# V2.net
KiCad netlist of a schematic drawn in Altium Designer
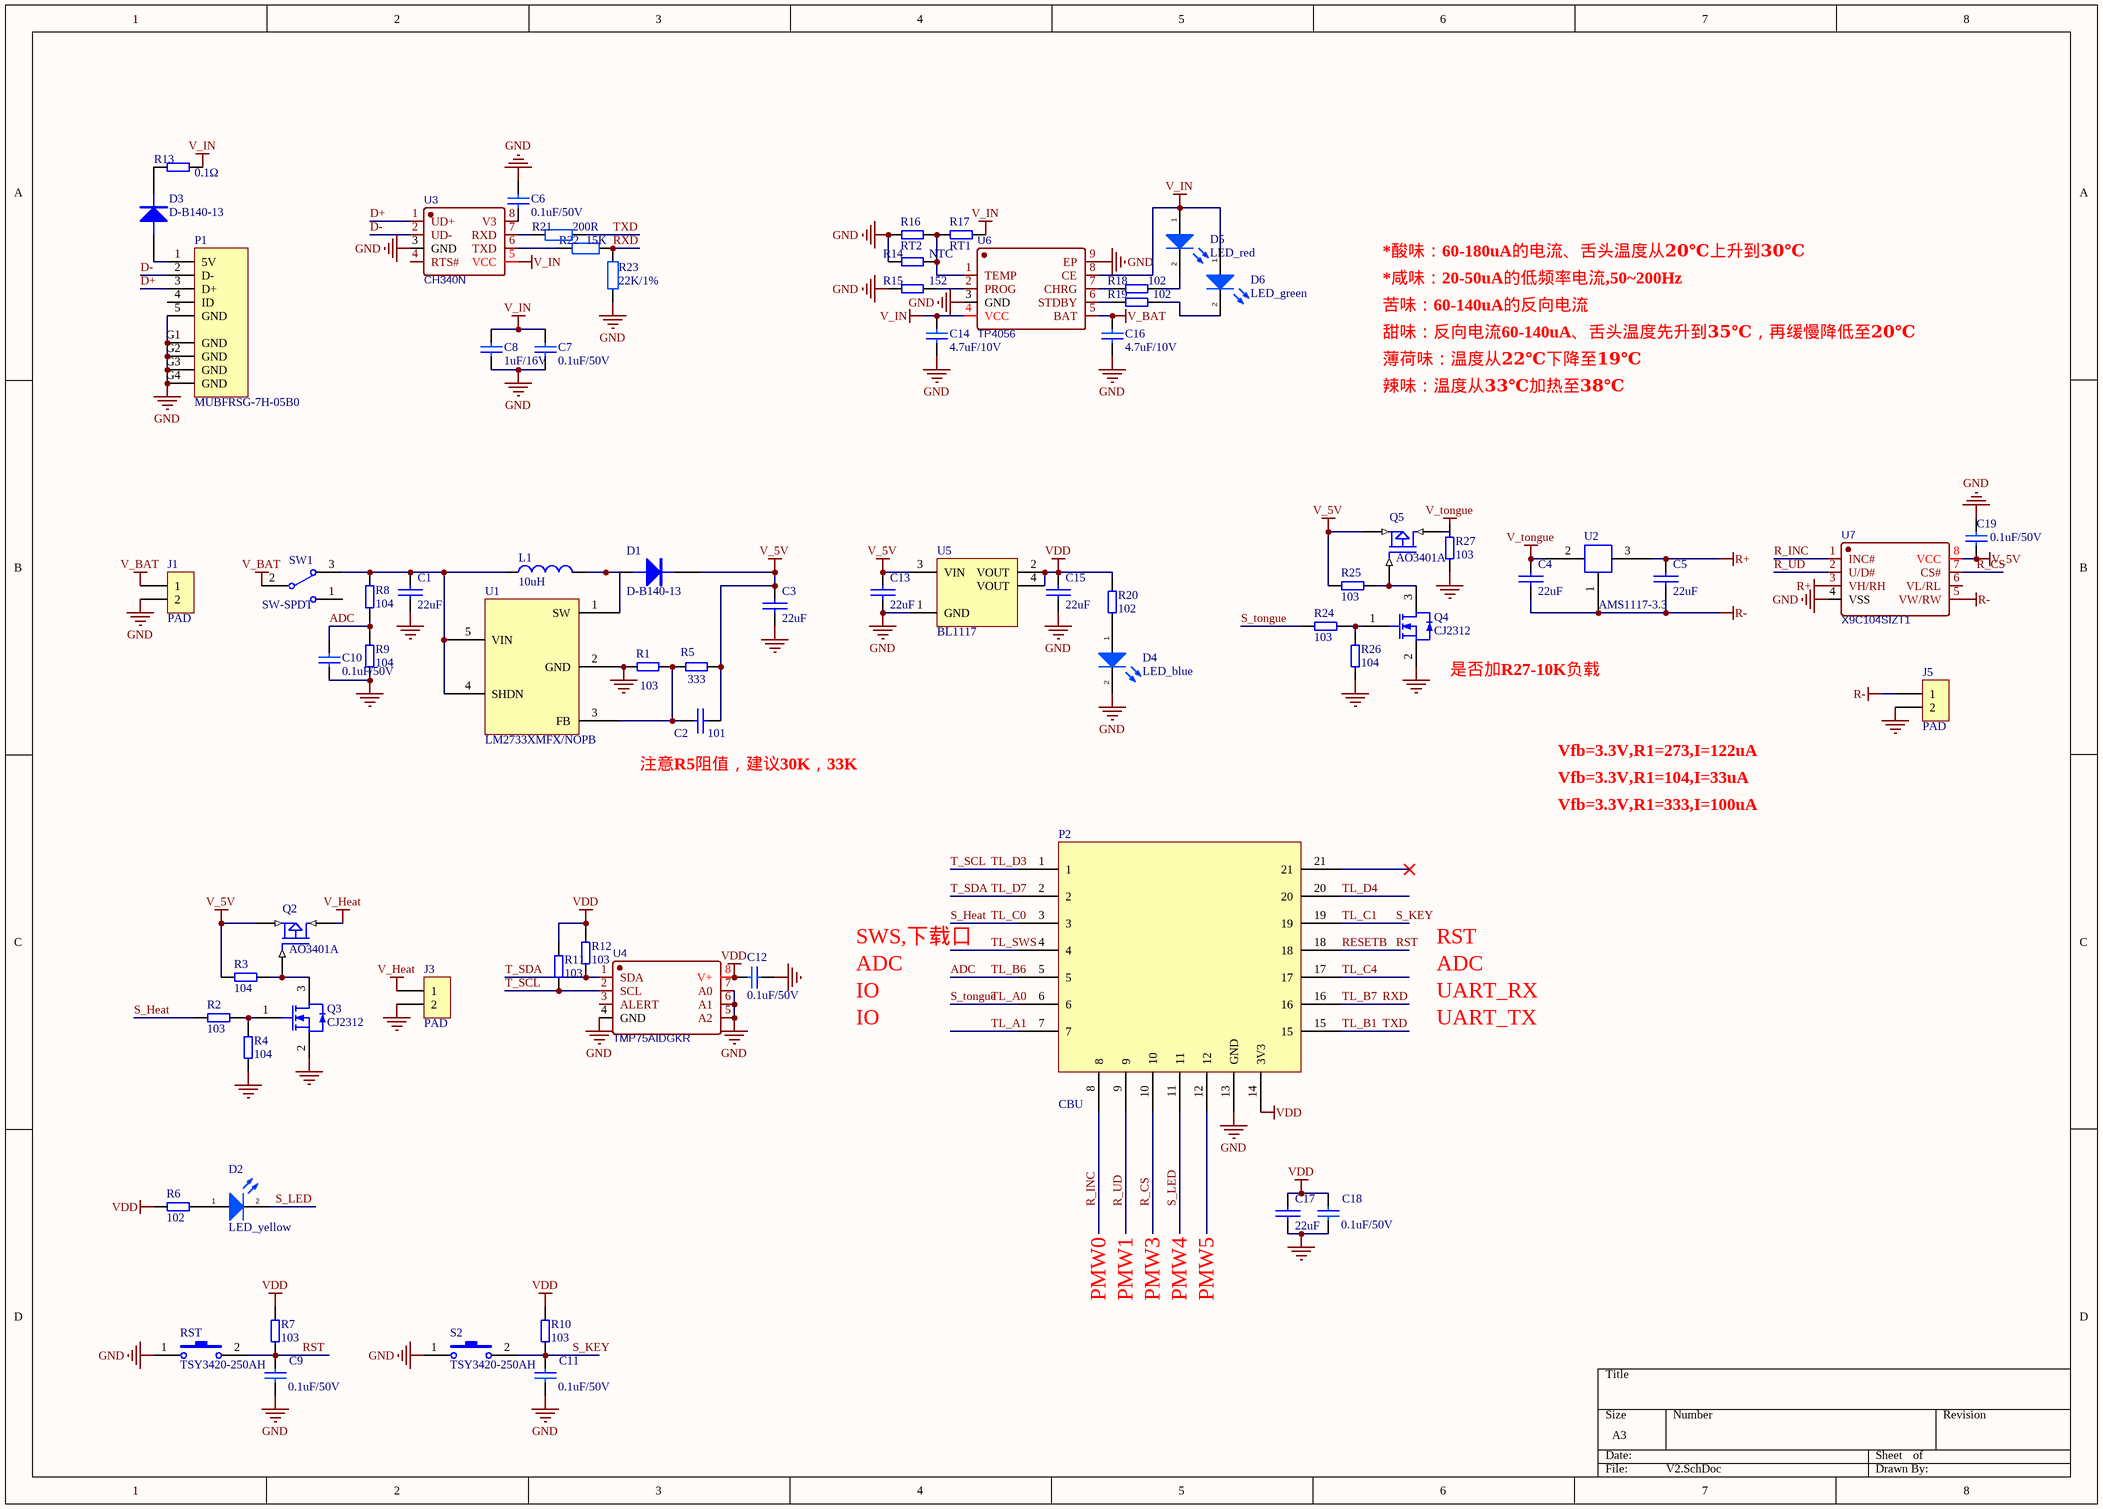
[diagram p0: V2.SchDoc]

(export (version "E")
  (design (tool "Eeschema 10.0.6"))
  (components
    (comp (ref "C1") (value "22uF") (footprint "C1206") (libsource (lib "altium-import") (part "root_0_C1_")))
    (comp (ref "C2")
      (value "101")
      (footprint "C0603")
      (description "Capacitor")
      (libsource (lib "先锋器件封装库") (part "CAP"))
    )
    (comp (ref "C3") (value "22uF") (footprint "C1206") (libsource (lib "altium-import") (part "root_0_C1_")))
    (comp (ref "C4") (value "22uF") (footprint "C1206") (libsource (lib "altium-import") (part "root_0_C1_")))
    (comp (ref "C5") (value "22uF") (footprint "C1206") (libsource (lib "altium-import") (part "root_0_C1_")))
    (comp (ref "C6")
      (value "0.1uF/50V")
      (footprint "C0603_GRM18")
      (description "无极性电容")
      (fields (field (name "PART NUMBER") "1.02.05.00834") (field (name "修改人") "system"))
      (libsource (lib "Database_Libs") (part "Capacitor - non polarized"))
    )
    (comp (ref "C7")
      (value "0.1uF/50V")
      (footprint "C0603_GRM18")
      (description "无极性电容")
      (fields (field (name "PART NUMBER") "1.02.05.00834") (field (name "修改人") "system"))
      (libsource (lib "Database_Libs") (part "Capacitor - non polarized"))
    )
    (comp (ref "C8")
      (value "1uF/16V")
      (footprint "C0603_GRM18")
      (description "无极性电容")
      (fields (field (name "PART NUMBER") "1.02.03.00181") (field (name "修改人") "system"))
      (libsource (lib "Database_Libs") (part "Capacitor - non polarized"))
    )
    (comp (ref "C9")
      (value "0.1uF/50V")
      (footprint "C0603_GRM18")
      (description "无极性电容")
      (fields (field (name "PART NUMBER") "1.02.05.00150") (field (name "修改人") "system"))
      (libsource (lib "Database_Libs") (part "Capacitor - non polarized"))
    )
    (comp (ref "C10")
      (value "0.1uF/50V")
      (footprint "C0603_GRM18")
      (description "无极性电容")
      (fields (field (name "PART NUMBER") "1.02.05.00150") (field (name "修改人") "system"))
      (libsource (lib "Database_Libs") (part "Capacitor - non polarized"))
    )
    (comp (ref "C11")
      (value "0.1uF/50V")
      (footprint "C0603_GRM18")
      (description "无极性电容")
      (fields (field (name "PART NUMBER") "1.02.05.00150") (field (name "修改人") "system"))
      (libsource (lib "Database_Libs") (part "Capacitor - non polarized"))
    )
    (comp (ref "C12")
      (value "0.1uF/50V")
      (footprint "C0603_GRM18")
      (description "无极性电容")
      (fields (field (name "PART NUMBER") "1.02.05.00150") (field (name "修改人") "system"))
      (libsource (lib "Database_Libs") (part "Capacitor - non polarized"))
    )
    (comp (ref "C13")
      (value "22uF")
      (footprint "C1206")
      (libsource (lib "altium-import") (part "root_0_C1_"))
    )
    (comp (ref "C14")
      (value "4.7uF/10V")
      (footprint "C0603_GRM18")
      (description "无极性电容")
      (fields (field (name "PART NUMBER") "1.02.05.00710") (field (name "修改人") "system"))
      (libsource (lib "Database_Libs") (part "Capacitor - non polarized"))
    )
    (comp (ref "C15")
      (value "22uF")
      (footprint "C1206")
      (libsource (lib "altium-import") (part "root_0_C1_"))
    )
    (comp (ref "C16")
      (value "4.7uF/10V")
      (footprint "C0603_GRM18")
      (description "无极性电容")
      (fields (field (name "PART NUMBER") "1.02.05.00710") (field (name "修改人") "system"))
      (libsource (lib "Database_Libs") (part "Capacitor - non polarized"))
    )
    (comp (ref "C17")
      (value "22uF")
      (footprint "C1206")
      (libsource (lib "altium-import") (part "root_0_C1_"))
    )
    (comp (ref "C18")
      (value "0.1uF/50V")
      (footprint "C0603_GRM18")
      (description "无极性电容")
      (fields (field (name "PART NUMBER") "1.02.05.00150") (field (name "修改人") "system"))
      (libsource (lib "Database_Libs") (part "Capacitor - non polarized"))
    )
    (comp (ref "C19")
      (value "0.1uF/50V")
      (footprint "C0603_GRM18")
      (description "无极性电容")
      (fields (field (name "PART NUMBER") "1.02.05.00150") (field (name "修改人") "system"))
      (libsource (lib "Database_Libs") (part "Capacitor - non polarized"))
    )
    (comp (ref "D1")
      (value "D-B140-13")
      (footprint "XF-SS12C")
      (description "Diode")
      (fields (field (name "SPECIFICATION") "D-B140-13"))
      (libsource (lib "先锋器件封装库") (part "DIODE"))
    )
    (comp (ref "D2")
      (value "LED_yellow")
      (footprint "LED0603")
      (description "LED")
      (fields (field (name "PART NUMBER") "1.06.02.00449") (field (name "修改人") "system"))
      (libsource (lib "Database_Libs") (part "LED"))
    )
    (comp (ref "D3")
      (value "D-B140-13")
      (footprint "XF-SS12C")
      (description "Diode")
      (fields (field (name "SPECIFICATION") "D-B140-13"))
      (libsource (lib "先锋器件封装库") (part "DIODE"))
    )
    (comp (ref "D4")
      (value "LED_blue")
      (footprint "LED0603")
      (description "LED")
      (fields (field (name "PART NUMBER") "1.06.02.00449") (field (name "修改人") "system"))
      (libsource (lib "Database_Libs") (part "LED"))
    )
    (comp (ref "D5")
      (value "LED_red")
      (footprint "LED0603")
      (description "LED")
      (fields (field (name "PART NUMBER") "1.06.02.00449") (field (name "修改人") "system"))
      (libsource (lib "Database_Libs") (part "LED"))
    )
    (comp (ref "D6")
      (value "LED_green")
      (footprint "LED0603")
      (description "LED")
      (fields (field (name "PART NUMBER") "1.06.02.00449") (field (name "修改人") "system"))
      (libsource (lib "Database_Libs") (part "LED"))
    )
    (comp (ref "J1")
      (value "PAD")
      (footprint "POW_5#")
      (description "Connector")
      (libsource (lib "altium-import") (part "root_0_CON2_"))
    )
    (comp (ref "J3")
      (value "PAD")
      (footprint "HDR1X2")
      (description "Connector")
      (libsource (lib "接插件") (part "CON2"))
    )
    (comp (ref "J5")
      (value "PAD")
      (footprint "HDR1X2")
      (description "Connector")
      (libsource (lib "接插件") (part "CON2"))
    )
    (comp (ref "L1")
      (value "10uH")
      (footprint "CD73")
      (description "Inductor")
      (fields (field (name "Comment") "4.7uH") (field (name "PUBLISHER") "Altium Limited"))
      (libsource (lib "altium-import") (part "root_0_Inductor_"))
    )
    (comp (ref "P1")
      (value "MUBFRSG-7H-05B0")
      (footprint "MIRCOUSB_5PIN-A")
      (description "USB")
      (fields (field (name "PART NUMBER") "1.16.99.00399") (field (name "修改人") "system"))
      (libsource (lib "Database_Libs") (part "USB_5p"))
    )
    (comp (ref "P2")
      (value "CBU")
      (footprint "PcbLib_Tuya:CBU-PCBA")
      (fields (field (name "PART NUMBER") "0110"))
      (libsource (lib "Database_Libs1") (part "CBU"))
    )
    (comp (ref "Q2")
      (value "AO3401A")
      (footprint "SOT-23")
      (description "MOSFET-P")
      (fields (field (name "SPECIFICATION") "AO3401A"))
      (libsource (lib "先锋器件封装库") (part "MOSFET-P"))
    )
    (comp (ref "Q3")
      (value "CJ2312")
      (footprint "SOT23-3")
      (description "N-Channel MOSFET")
      (fields
        (field (name "PART NUMBER") "1.06.11.00008")
        (field (name "ORCAD LIBRARY PATH") "‪Z:\\tuya_lib\\sch-lib\\DISCRETE.OLB")
        (field (name "修改人") "system")
      )
      (libsource (lib "Database_Libs") (part "MOSFET-N"))
    )
    (comp (ref "Q4")
      (value "CJ2312")
      (footprint "SOT23-3")
      (description "N-Channel MOSFET")
      (fields
        (field (name "PART NUMBER") "1.06.11.00008")
        (field (name "ORCAD LIBRARY PATH") "‪Z:\\tuya_lib\\sch-lib\\DISCRETE.OLB")
        (field (name "修改人") "system")
      )
      (libsource (lib "Database_Libs") (part "MOSFET-N"))
    )
    (comp (ref "Q5")
      (value "AO3401A")
      (footprint "SOT-23")
      (description "MOSFET-P")
      (fields (field (name "SPECIFICATION") "AO3401A"))
      (libsource (lib "先锋器件封装库") (part "MOSFET-P"))
    )
    (comp (ref "R1")
      (value "103")
      (footprint "R0603")
      (description "RES")
      (libsource (lib "先锋器件封装库") (part "RES-1"))
    )
    (comp (ref "R2")
      (value "103")
      (footprint "R0603")
      (description "RES")
      (libsource (lib "先锋器件封装库") (part "RES-1"))
    )
    (comp (ref "R3")
      (value "104")
      (footprint "R0603")
      (description "RES")
      (libsource (lib "先锋器件封装库") (part "RES-1"))
    )
    (comp (ref "R4")
      (value "104")
      (footprint "R0603")
      (description "RES")
      (libsource (lib "先锋器件封装库") (part "RES-1"))
    )
    (comp (ref "R5")
      (value "333")
      (footprint "R0603")
      (description "RES")
      (libsource (lib "先锋器件封装库") (part "RES-1"))
    )
    (comp (ref "R6")
      (value "102")
      (footprint "R0603")
      (description "RES")
      (libsource (lib "先锋器件封装库") (part "RES-1"))
    )
    (comp (ref "R7")
      (value "103")
      (footprint "R0603")
      (description "RES")
      (libsource (lib "先锋器件封装库") (part "RES-1"))
    )
    (comp (ref "R8")
      (value "104")
      (footprint "R0603")
      (description "RES")
      (libsource (lib "先锋器件封装库") (part "RES-1"))
    )
    (comp (ref "R9")
      (value "104")
      (footprint "R0603")
      (description "RES")
      (libsource (lib "先锋器件封装库") (part "RES-1"))
    )
    (comp (ref "R10")
      (value "103")
      (footprint "R0603")
      (description "RES")
      (libsource (lib "先锋器件封装库") (part "RES-1"))
    )
    (comp (ref "R11")
      (value "103")
      (footprint "R0603")
      (description "RES")
      (libsource (lib "先锋器件封装库") (part "RES-1"))
    )
    (comp (ref "R12")
      (value "103")
      (footprint "R0603")
      (description "RES")
      (libsource (lib "先锋器件封装库") (part "RES-1"))
    )
    (comp (ref "R13")
      (value "0.1Ω")
      (footprint "R0603")
      (description "RES")
      (libsource (lib "先锋器件封装库") (part "RES-1"))
    )
    (comp (ref "R14")
      (value "NTC")
      (footprint "R0603")
      (description "RES")
      (libsource (lib "先锋器件封装库") (part "RES-1"))
    )
    (comp (ref "R15")
      (value "152")
      (footprint "R0603")
      (description "RES")
      (libsource (lib "先锋器件封装库") (part "RES-1"))
    )
    (comp (ref "R16")
      (value "RT2")
      (footprint "R0603")
      (description "RES")
      (libsource (lib "先锋器件封装库") (part "RES-1"))
    )
    (comp (ref "R17")
      (value "RT1")
      (footprint "R0603")
      (description "RES")
      (libsource (lib "先锋器件封装库") (part "RES-1"))
    )
    (comp (ref "R18")
      (value "102")
      (footprint "R0603")
      (description "RES")
      (libsource (lib "先锋器件封装库") (part "RES-1"))
    )
    (comp (ref "R19")
      (value "102")
      (footprint "R0603")
      (description "RES")
      (libsource (lib "先锋器件封装库") (part "RES-1"))
    )
    (comp (ref "R20")
      (value "102")
      (footprint "R0603")
      (description "RES")
      (libsource (lib "先锋器件封装库") (part "RES-1"))
    )
    (comp (ref "R21")
      (value "200R")
      (footprint "R0603")
      (description "电阻")
      (fields (field (name "PART NUMBER") "1.01.01.00808") (field (name "修改人") "system"))
      (libsource (lib "Database_Libs") (part "Resistor"))
    )
    (comp (ref "R22")
      (value "15K")
      (footprint "R0603")
      (description "电阻")
      (fields (field (name "PART NUMBER") "1.01.01.01301") (field (name "修改人") "system"))
      (libsource (lib "Database_Libs") (part "Resistor"))
    )
    (comp (ref "R23")
      (value "22K/1%")
      (footprint "R0603")
      (description "电阻")
      (fields (field (name "PART NUMBER") "1.01.01.01030") (field (name "修改人") "system"))
      (libsource (lib "") (part "Resistor_1"))
    )
    (comp (ref "R24")
      (value "103")
      (footprint "R0603")
      (description "RES")
      (libsource (lib "先锋器件封装库") (part "RES-1"))
    )
    (comp (ref "R25")
      (value "103")
      (footprint "R0603")
      (description "RES")
      (libsource (lib "先锋器件封装库") (part "RES-1"))
    )
    (comp (ref "R26")
      (value "104")
      (footprint "R0603")
      (description "RES")
      (libsource (lib "先锋器件封装库") (part "RES-1"))
    )
    (comp (ref "R27")
      (value "103")
      (footprint "R0603")
      (description "RES")
      (libsource (lib "先锋器件封装库") (part "RES-1"))
    )
    (comp (ref "RST")
      (value "TSY3420-250AH")
      (footprint "SW-PB2_SMT-3X4")
      (description "2pin轻触开关（无固定脚）")
      (fields (field (name "PART NUMBER") "1.13.04.00024") (field (name "修改人") "system"))
      (libsource (lib "Database_Libs") (part "SW-PB2"))
    )
    (comp (ref "S2")
      (value "TSY3420-250AH")
      (footprint "SW-PB2_SMT-3X4")
      (description "2pin轻触开关（无固定脚）")
      (fields (field (name "PART NUMBER") "1.13.04.00024") (field (name "修改人") "system"))
      (libsource (lib "Database_Libs") (part "SW-PB2"))
    )
    (comp (ref "SW1")
      (value "SW-SPDT")
      (footprint "pow_switch")
      (description "SPDT Subminiature Toggle Switch, Right Angle Mounting, Vertical Actuation")
      (fields (field (name "PUBLISHER") "Altium Limited"))
      (libsource (lib "Miscellaneous Devices") (part "SW-SPDT"))
    )
    (comp (ref "U1")
      (value "LM2733XMFX/NOPB")
      (footprint "SOT23-5")
      (description "LM2733")
      (fields (field (name "SPECIFICATION") "LM2733XMFX/NOPB"))
      (libsource (lib "先锋器件封装库") (part "LM2733"))
    )
    (comp (ref "U2") (value "AMS1117-3.3") (footprint "SOT-89C") (libsource (lib "*") (part "WYK")))
    (comp (ref "U3")
      (value "CH340N")
      (footprint "SOP-8")
      (fields (field (name "BOM_SUPPLIER PART") "C506813") (field (name "CONTRIBUTOR") "LCSC"))
      (libsource (lib "TY") (part "CH340N"))
    )
    (comp (ref "U4")
      (value "TMP75AIDGKR")
      (footprint "VSSOP-8_L3.0-W3.0-P0.65-LS5.0-BL")
      (fields (field (name "BOM_SUPPLIER PART") "C105258") (field (name "CONTRIBUTOR") "LCSC"))
      (libsource (lib "TY") (part "TMP75AIDGKR"))
    )
    (comp (ref "U5")
      (value "BL1117")
      (footprint "SOT-223")
      (description "线性稳压源")
      (fields (field (name "PART NUMBER") "1.05.99.00236") (field (name "修改人") "system"))
      (libsource (lib "Database_Libs") (part "LDO_REG1117"))
    )
    (comp (ref "U6")
      (value "TP4056")
      (footprint "ESOP-8")
      (fields (field (name "BOM_SUPPLIER PART") "C725790") (field (name "CONTRIBUTOR") "LCSC"))
      (libsource (lib "TY") (part "TP4056_C725790"))
    )
    (comp (ref "U7")
      (value "X9C104SIZT1")
      (footprint "SOIC-8_L4.9-W3.9-P1.27-LS6.0-BL")
      (fields (field (name "BOM_SUPPLIER PART") "C11979"))
      (libsource (lib "TY") (part "X9C104SIZT1"))
    )
  )
  (nets
    (net (code "1") (name "/ADC") (class "Default")
      (node (ref "C10") (pin "2") (pinfunction "2_2") (pintype "passive"))
      (node (ref "P2") (pin "5") (pinfunction "5_5") (pintype "passive"))
      (node (ref "R8") (pin "1") (pintype "passive"))
      (node (ref "R9") (pin "2") (pintype "passive"))
    )
    (net (code "2") (name "/D+") (class "Default")
      (node (ref "P1") (pin "3") (pinfunction "D+_3") (pintype "passive"))
      (node (ref "U3") (pin "1") (pinfunction "UD+_1") (pintype "passive"))
    )
    (net (code "3") (name "/D-") (class "Default")
      (node (ref "P1") (pin "2") (pinfunction "D-_2") (pintype "passive"))
      (node (ref "U3") (pin "2") (pinfunction "UD-_2") (pintype "passive"))
    )
    (net (code "4") (name "/RESETB") (class "Default")
      (node (ref "C9") (pin "1") (pinfunction "1_1") (pintype "passive"))
      (node (ref "P2") (pin "18") (pinfunction "18_18") (pintype "passive"))
      (node (ref "R7") (pin "1") (pintype "passive"))
      (node (ref "RST") (pin "2") (pinfunction "2_2") (pintype "passive"))
    )
    (net (code "5") (name "/RXD") (class "Default")
      (node (ref "P2") (pin "16") (pinfunction "16_16") (pintype "passive"))
      (node (ref "R22") (pin "2") (pinfunction "2_2") (pintype "passive"))
      (node (ref "R23") (pin "2") (pinfunction "2_2") (pintype "passive"))
    )
    (net (code "6") (name "/R_CS") (class "Default")
      (node (ref "P2") (pin "10") (pinfunction "10_10") (pintype "passive"))
      (node (ref "U7") (pin "7") (pinfunction "CS#_7") (pintype "passive"))
    )
    (net (code "7") (name "/R_INC") (class "Default")
      (node (ref "P2") (pin "8") (pinfunction "8_8") (pintype "passive"))
      (node (ref "U7") (pin "1") (pinfunction "INC#_1") (pintype "passive"))
    )
    (net (code "8") (name "/R_UD") (class "Default")
      (node (ref "P2") (pin "9") (pinfunction "9_9") (pintype "passive"))
      (node (ref "U7") (pin "2") (pinfunction "U/D#_2") (pintype "passive"))
    )
    (net (code "9") (name "/S_Heat") (class "Default")
      (node (ref "P2") (pin "3") (pinfunction "3_3") (pintype "passive"))
      (node (ref "R2") (pin "1") (pintype "passive"))
    )
    (net (code "10") (name "/S_KEY") (class "Default")
      (node (ref "C11") (pin "1") (pinfunction "1_1") (pintype "passive"))
      (node (ref "P2") (pin "19") (pinfunction "19_19") (pintype "passive"))
      (node (ref "R10") (pin "1") (pintype "passive"))
      (node (ref "S2") (pin "2") (pinfunction "2_2") (pintype "passive"))
    )
    (net (code "11") (name "/S_LED") (class "Default")
      (node (ref "D2") (pin "2") (pinfunction "2_2") (pintype "passive"))
      (node (ref "P2") (pin "11") (pinfunction "11_11") (pintype "passive"))
    )
    (net (code "12") (name "/S_tongue") (class "Default")
      (node (ref "P2") (pin "6") (pinfunction "6_6") (pintype "passive"))
      (node (ref "R24") (pin "1") (pintype "passive"))
    )
    (net (code "13") (name "/TL_A1") (class "Default")
      (node (ref "P2") (pin "7") (pinfunction "7_7") (pintype "passive"))
    )
    (net (code "14") (name "/TL_B1") (class "Default")
      (node (ref "P2") (pin "15") (pinfunction "15_15") (pintype "passive"))
      (node (ref "R21") (pin "2") (pinfunction "2_2") (pintype "passive"))
    )
    (net (code "15") (name "/TL_C4") (class "Default")
      (node (ref "P2") (pin "17") (pinfunction "17_17") (pintype "passive"))
    )
    (net (code "16") (name "/TL_D3") (class "Default")
      (node (ref "P2") (pin "1") (pinfunction "1_1") (pintype "passive"))
      (node (ref "R11") (pin "1") (pintype "passive"))
      (node (ref "U4") (pin "2") (pinfunction "SCL_2") (pintype "passive"))
    )
    (net (code "17") (name "/TL_D4") (class "Default")
      (node (ref "P2") (pin "20") (pinfunction "20_20") (pintype "passive"))
    )
    (net (code "18") (name "/TL_D7") (class "Default")
      (node (ref "P2") (pin "2") (pinfunction "2_2") (pintype "passive"))
      (node (ref "R12") (pin "1") (pintype "passive"))
      (node (ref "U4") (pin "1") (pinfunction "SDA_1") (pintype "passive"))
    )
    (net (code "19") (name "/TL_SWS") (class "Default")
      (node (ref "P2") (pin "4") (pinfunction "4_4") (pintype "passive"))
    )
    (net (code "20") (name "GND") (class "Default")
      (node (ref "C1") (pin "2") (pinfunction "2_2") (pintype "passive"))
      (node (ref "C10") (pin "1") (pinfunction "1_1") (pintype "passive"))
      (node (ref "C11") (pin "2") (pinfunction "2_2") (pintype "passive"))
      (node (ref "C12") (pin "1") (pinfunction "1_1") (pintype "passive"))
      (node (ref "C13") (pin "2") (pinfunction "2_2") (pintype "passive"))
      (node (ref "C14") (pin "1") (pinfunction "1_1") (pintype "passive"))
      (node (ref "C15") (pin "2") (pinfunction "2_2") (pintype "passive"))
      (node (ref "C16") (pin "1") (pinfunction "1_1") (pintype "passive"))
      (node (ref "C17") (pin "2") (pinfunction "2_2") (pintype "passive"))
      (node (ref "C18") (pin "2") (pinfunction "2_2") (pintype "passive"))
      (node (ref "C19") (pin "2") (pinfunction "2_2") (pintype "passive"))
      (node (ref "C3") (pin "2") (pinfunction "2_2") (pintype "passive"))
      (node (ref "C6") (pin "2") (pinfunction "2_2") (pintype "passive"))
      (node (ref "C7") (pin "1") (pinfunction "1_1") (pintype "passive"))
      (node (ref "C8") (pin "1") (pinfunction "1_1") (pintype "passive"))
      (node (ref "C9") (pin "2") (pinfunction "2_2") (pintype "passive"))
      (node (ref "D4") (pin "2") (pinfunction "2_2") (pintype "passive"))
      (node (ref "J1") (pin "2") (pinfunction "2_2") (pintype "passive"))
      (node (ref "J3") (pin "2") (pinfunction "2_2") (pintype "passive"))
      (node (ref "J5") (pin "2") (pinfunction "2_2") (pintype "passive"))
      (node (ref "P1") (pin "5") (pinfunction "GND_5") (pintype "passive"))
      (node (ref "P1") (pin "G1") (pinfunction "GND_G1") (pintype "passive"))
      (node (ref "P1") (pin "G2") (pinfunction "GND_G2") (pintype "passive"))
      (node (ref "P1") (pin "G3") (pinfunction "GND_G3") (pintype "passive"))
      (node (ref "P1") (pin "G4") (pinfunction "GND_G4") (pintype "passive"))
      (node (ref "P2") (pin "13") (pinfunction "GND_13") (pintype "passive"))
      (node (ref "Q3") (pin "2") (pinfunction "S_2") (pintype "passive"))
      (node (ref "Q4") (pin "2") (pinfunction "S_2") (pintype "passive"))
      (node (ref "R1") (pin "1") (pintype "passive"))
      (node (ref "R14") (pin "2") (pintype "passive"))
      (node (ref "R15") (pin "2") (pintype "passive"))
      (node (ref "R16") (pin "1") (pintype "passive"))
      (node (ref "R23") (pin "1") (pinfunction "1_1") (pintype "passive"))
      (node (ref "R26") (pin "1") (pintype "passive"))
      (node (ref "R27") (pin "1") (pintype "passive"))
      (node (ref "R4") (pin "1") (pintype "passive"))
      (node (ref "R9") (pin "1") (pintype "passive"))
      (node (ref "RST") (pin "1") (pinfunction "1_1") (pintype "passive"))
      (node (ref "S2") (pin "1") (pinfunction "1_1") (pintype "passive"))
      (node (ref "U1") (pin "2") (pinfunction "GND_2") (pintype "passive"))
      (node (ref "U3") (pin "3") (pinfunction "GND_3") (pintype "passive"))
      (node (ref "U4") (pin "4") (pinfunction "GND_4") (pintype "passive"))
      (node (ref "U4") (pin "5") (pinfunction "A2_5") (pintype "passive"))
      (node (ref "U4") (pin "6") (pinfunction "A1_6") (pintype "passive"))
      (node (ref "U4") (pin "7") (pinfunction "A0_7") (pintype "passive"))
      (node (ref "U5") (pin "1") (pinfunction "GND_1") (pintype "passive"))
      (node (ref "U6") (pin "3") (pinfunction "GND_3") (pintype "passive"))
      (node (ref "U6") (pin "9") (pinfunction "EP_9") (pintype "passive"))
      (node (ref "U7") (pin "4") (pinfunction "VSS_4") (pintype "passive"))
    )
    (net (code "21") (name "Net-(D2-Pad1)") (class "Default")
      (node (ref "D2") (pin "1") (pinfunction "1_1") (pintype "passive"))
      (node (ref "R6") (pin "2") (pintype "passive"))
    )
    (net (code "22") (name "Net-(D3-PadK)") (class "Default")
      (node (ref "D3") (pin "K") (pinfunction "K_K") (pintype "passive"))
      (node (ref "R13") (pin "2") (pintype "passive"))
    )
    (net (code "23") (name "Net-(D4-Pad1)") (class "Default")
      (node (ref "D4") (pin "1") (pinfunction "1_1") (pintype "passive"))
      (node (ref "R20") (pin "1") (pintype "passive"))
    )
    (net (code "24") (name "Net-(D5-Pad2)") (class "Default")
      (node (ref "D5") (pin "2") (pinfunction "2_2") (pintype "passive"))
      (node (ref "R18") (pin "2") (pintype "passive"))
    )
    (net (code "25") (name "Net-(D6-Pad2)") (class "Default")
      (node (ref "D6") (pin "2") (pinfunction "2_2") (pintype "passive"))
      (node (ref "R19") (pin "1") (pintype "passive"))
    )
    (net (code "26") (name "Net-(P1-5V)") (class "Default")
      (node (ref "D3") (pin "A") (pinfunction "A_A") (pintype "passive"))
      (node (ref "P1") (pin "1") (pinfunction "5V_1") (pintype "passive"))
    )
    (net (code "27") (name "Net-(Q3-D)") (class "Default")
      (node (ref "Q2") (pin "G") (pinfunction "G_G") (pintype "input"))
      (node (ref "Q3") (pin "3") (pinfunction "D_3") (pintype "passive"))
      (node (ref "R3") (pin "2") (pintype "passive"))
    )
    (net (code "28") (name "Net-(Q3-G)") (class "Default")
      (node (ref "Q3") (pin "1") (pinfunction "G_1") (pintype "passive"))
      (node (ref "R2") (pin "2") (pintype "passive"))
      (node (ref "R4") (pin "2") (pintype "passive"))
    )
    (net (code "29") (name "Net-(Q4-D)") (class "Default")
      (node (ref "Q4") (pin "3") (pinfunction "D_3") (pintype "passive"))
      (node (ref "Q5") (pin "G") (pinfunction "G_G") (pintype "input"))
      (node (ref "R25") (pin "2") (pintype "passive"))
    )
    (net (code "30") (name "Net-(Q4-G)") (class "Default")
      (node (ref "Q4") (pin "1") (pinfunction "G_1") (pintype "passive"))
      (node (ref "R24") (pin "2") (pintype "passive"))
      (node (ref "R26") (pin "2") (pintype "passive"))
    )
    (net (code "31") (name "Net-(U1-FB)") (class "Default")
      (node (ref "C2") (pin "2") (pinfunction "2_2") (pintype "passive"))
      (node (ref "R1") (pin "2") (pintype "passive"))
      (node (ref "R5") (pin "2") (pintype "passive"))
      (node (ref "U1") (pin "3") (pinfunction "FB_3") (pintype "passive"))
    )
    (net (code "32") (name "Net-(U1-SHDN)") (class "Default")
      (node (ref "C1") (pin "1") (pinfunction "1_1") (pintype "passive"))
      (node (ref "L1") (pin "1") (pinfunction "1_1") (pintype "passive"))
      (node (ref "R8") (pin "2") (pintype "passive"))
      (node (ref "SW1") (pin "3") (pinfunction "3_3") (pintype "passive"))
      (node (ref "U1") (pin "4") (pinfunction "SHDN_4") (pintype "passive"))
      (node (ref "U1") (pin "5") (pinfunction "VIN_5") (pintype "passive"))
    )
    (net (code "33") (name "Net-(U1-SW)") (class "Default")
      (node (ref "D1") (pin "A") (pinfunction "A_A") (pintype "passive"))
      (node (ref "L1") (pin "2") (pinfunction "2_2") (pintype "passive"))
      (node (ref "U1") (pin "1") (pinfunction "SW_1") (pintype "passive"))
    )
    (net (code "34") (name "Net-(U3-RXD)") (class "Default")
      (node (ref "R21") (pin "1") (pinfunction "1_1") (pintype "passive"))
      (node (ref "U3") (pin "7") (pinfunction "RXD_7") (pintype "passive"))
    )
    (net (code "35") (name "Net-(U3-TXD)") (class "Default")
      (node (ref "R22") (pin "1") (pinfunction "1_1") (pintype "passive"))
      (node (ref "U3") (pin "6") (pinfunction "TXD_6") (pintype "passive"))
    )
    (net (code "36") (name "Net-(U3-V3)") (class "Default")
      (node (ref "C6") (pin "1") (pinfunction "1_1") (pintype "passive"))
      (node (ref "U3") (pin "8") (pinfunction "V3_8") (pintype "passive"))
    )
    (net (code "37") (name "Net-(U6-CHRG)") (class "Default")
      (node (ref "R18") (pin "1") (pintype "passive"))
      (node (ref "U6") (pin "7") (pinfunction "CHRG_7") (pintype "passive"))
    )
    (net (code "38") (name "Net-(U6-PROG)") (class "Default")
      (node (ref "R15") (pin "1") (pintype "passive"))
      (node (ref "U6") (pin "2") (pinfunction "PROG_2") (pintype "passive"))
    )
    (net (code "39") (name "Net-(U6-STDBY)") (class "Default")
      (node (ref "R19") (pin "2") (pintype "passive"))
      (node (ref "U6") (pin "6") (pinfunction "STDBY_6") (pintype "passive"))
    )
    (net (code "40") (name "Net-(U6-TEMP)") (class "Default")
      (node (ref "R14") (pin "1") (pintype "passive"))
      (node (ref "R16") (pin "2") (pintype "passive"))
      (node (ref "R17") (pin "2") (pintype "passive"))
      (node (ref "U6") (pin "1") (pinfunction "TEMP_1") (pintype "passive"))
    )
    (net (code "41") (name "R+") (class "Default")
      (node (ref "C5") (pin "1") (pinfunction "1_1") (pintype "passive"))
      (node (ref "U2") (pin "3") (pintype "passive"))
      (node (ref "U7") (pin "3") (pinfunction "VH/RH_3") (pintype "passive"))
    )
    (net (code "42") (name "R-") (class "Default")
      (node (ref "C4") (pin "2") (pinfunction "2_2") (pintype "passive"))
      (node (ref "C5") (pin "2") (pinfunction "2_2") (pintype "passive"))
      (node (ref "J5") (pin "1") (pinfunction "1_1") (pintype "passive"))
      (node (ref "U2") (pin "1") (pintype "passive"))
      (node (ref "U7") (pin "5") (pinfunction "VW/RW_5") (pintype "passive"))
    )
    (net (code "43") (name "VDD") (class "Default")
      (node (ref "C12") (pin "2") (pinfunction "2_2") (pintype "passive"))
      (node (ref "C15") (pin "1") (pinfunction "1_1") (pintype "passive"))
      (node (ref "C17") (pin "1") (pinfunction "1_1") (pintype "passive"))
      (node (ref "C18") (pin "1") (pinfunction "1_1") (pintype "passive"))
      (node (ref "P2") (pin "14") (pinfunction "3V3_14") (pintype "passive"))
      (node (ref "R10") (pin "2") (pintype "passive"))
      (node (ref "R11") (pin "2") (pintype "passive"))
      (node (ref "R12") (pin "2") (pintype "passive"))
      (node (ref "R20") (pin "2") (pintype "passive"))
      (node (ref "R6") (pin "1") (pintype "passive"))
      (node (ref "R7") (pin "2") (pintype "passive"))
      (node (ref "U4") (pin "8") (pinfunction "V+_8") (pintype "passive"))
      (node (ref "U5") (pin "2") (pinfunction "VOUT_2") (pintype "passive"))
      (node (ref "U5") (pin "4") (pinfunction "VOUT_4") (pintype "passive"))
    )
    (net (code "44") (name "V_5V") (class "Default")
      (node (ref "C13") (pin "1") (pinfunction "1_1") (pintype "passive"))
      (node (ref "C19") (pin "1") (pinfunction "1_1") (pintype "passive"))
      (node (ref "C2") (pin "1") (pinfunction "1_1") (pintype "passive"))
      (node (ref "C3") (pin "1") (pinfunction "1_1") (pintype "passive"))
      (node (ref "D1") (pin "K") (pinfunction "K_K") (pintype "passive"))
      (node (ref "Q2") (pin "S") (pinfunction "S_S") (pintype "input"))
      (node (ref "Q5") (pin "S") (pinfunction "S_S") (pintype "input"))
      (node (ref "R25") (pin "1") (pintype "passive"))
      (node (ref "R3") (pin "1") (pintype "passive"))
      (node (ref "R5") (pin "1") (pintype "passive"))
      (node (ref "U5") (pin "3") (pinfunction "VIN_3") (pintype "passive"))
      (node (ref "U7") (pin "8") (pinfunction "VCC_8") (pintype "passive"))
    )
    (net (code "45") (name "V_BAT") (class "Default")
      (node (ref "C16") (pin "2") (pinfunction "2_2") (pintype "passive"))
      (node (ref "J1") (pin "1") (pinfunction "1_1") (pintype "passive"))
      (node (ref "SW1") (pin "2") (pinfunction "2_2") (pintype "passive"))
      (node (ref "U6") (pin "5") (pinfunction "BAT_5") (pintype "passive"))
    )
    (net (code "46") (name "V_Heat") (class "Default")
      (node (ref "J3") (pin "1") (pinfunction "1_1") (pintype "passive"))
      (node (ref "Q2") (pin "D") (pinfunction "D_D") (pintype "input"))
    )
    (net (code "47") (name "V_IN") (class "Default")
      (node (ref "C14") (pin "2") (pinfunction "2_2") (pintype "passive"))
      (node (ref "C7") (pin "2") (pinfunction "2_2") (pintype "passive"))
      (node (ref "C8") (pin "2") (pinfunction "2_2") (pintype "passive"))
      (node (ref "D5") (pin "1") (pinfunction "1_1") (pintype "passive"))
      (node (ref "D6") (pin "1") (pinfunction "1_1") (pintype "passive"))
      (node (ref "R13") (pin "1") (pintype "passive"))
      (node (ref "R17") (pin "1") (pintype "passive"))
      (node (ref "U3") (pin "5") (pinfunction "VCC_5") (pintype "passive"))
      (node (ref "U6") (pin "4") (pinfunction "VCC_4") (pintype "passive"))
      (node (ref "U6") (pin "8") (pinfunction "CE_8") (pintype "passive"))
    )
    (net (code "48") (name "V_tongue") (class "Default")
      (node (ref "C4") (pin "1") (pinfunction "1_1") (pintype "passive"))
      (node (ref "Q5") (pin "D") (pinfunction "D_D") (pintype "input"))
      (node (ref "U2") (pin "2") (pintype "passive"))
    )
    (net (code "49") (name "unconnected-(P1-ID-Pad4)") (class "Default")
      (node (ref "P1") (pin "4") (pinfunction "ID_4") (pintype "passive"))
    )
    (net (code "50") (name "unconnected-(P2-Pad12)") (class "Default")
      (node (ref "P2") (pin "12") (pinfunction "12_12") (pintype "passive"))
    )
    (net (code "51") (name "unconnected-(P2-Pad21)") (class "Default")
      (node (ref "P2") (pin "21") (pinfunction "21_21") (pintype "passive+no_connect"))
    )
    (net (code "52") (name "unconnected-(R27-Pad2)") (class "Default")
      (node (ref "R27") (pin "2") (pintype "passive"))
    )
    (net (code "53") (name "unconnected-(SW1-Pad1)") (class "Default")
      (node (ref "SW1") (pin "1") (pinfunction "1_1") (pintype "passive"))
    )
    (net (code "54") (name "unconnected-(U3-RTS#-Pad4)") (class "Default")
      (node (ref "U3") (pin "4") (pinfunction "RTS#_4") (pintype "passive"))
    )
    (net (code "55") (name "unconnected-(U4-ALERT-Pad3)") (class "Default")
      (node (ref "U4") (pin "3") (pinfunction "ALERT_3") (pintype "passive"))
    )
    (net (code "56") (name "unconnected-(U7-VL{slash}RL-Pad6)") (class "Default")
      (node (ref "U7") (pin "6") (pinfunction "VL/RL_6") (pintype "passive"))
    )
  )
)
